# TD4Lite.net
KiCad netlist of a schematic drawn in EAGLE
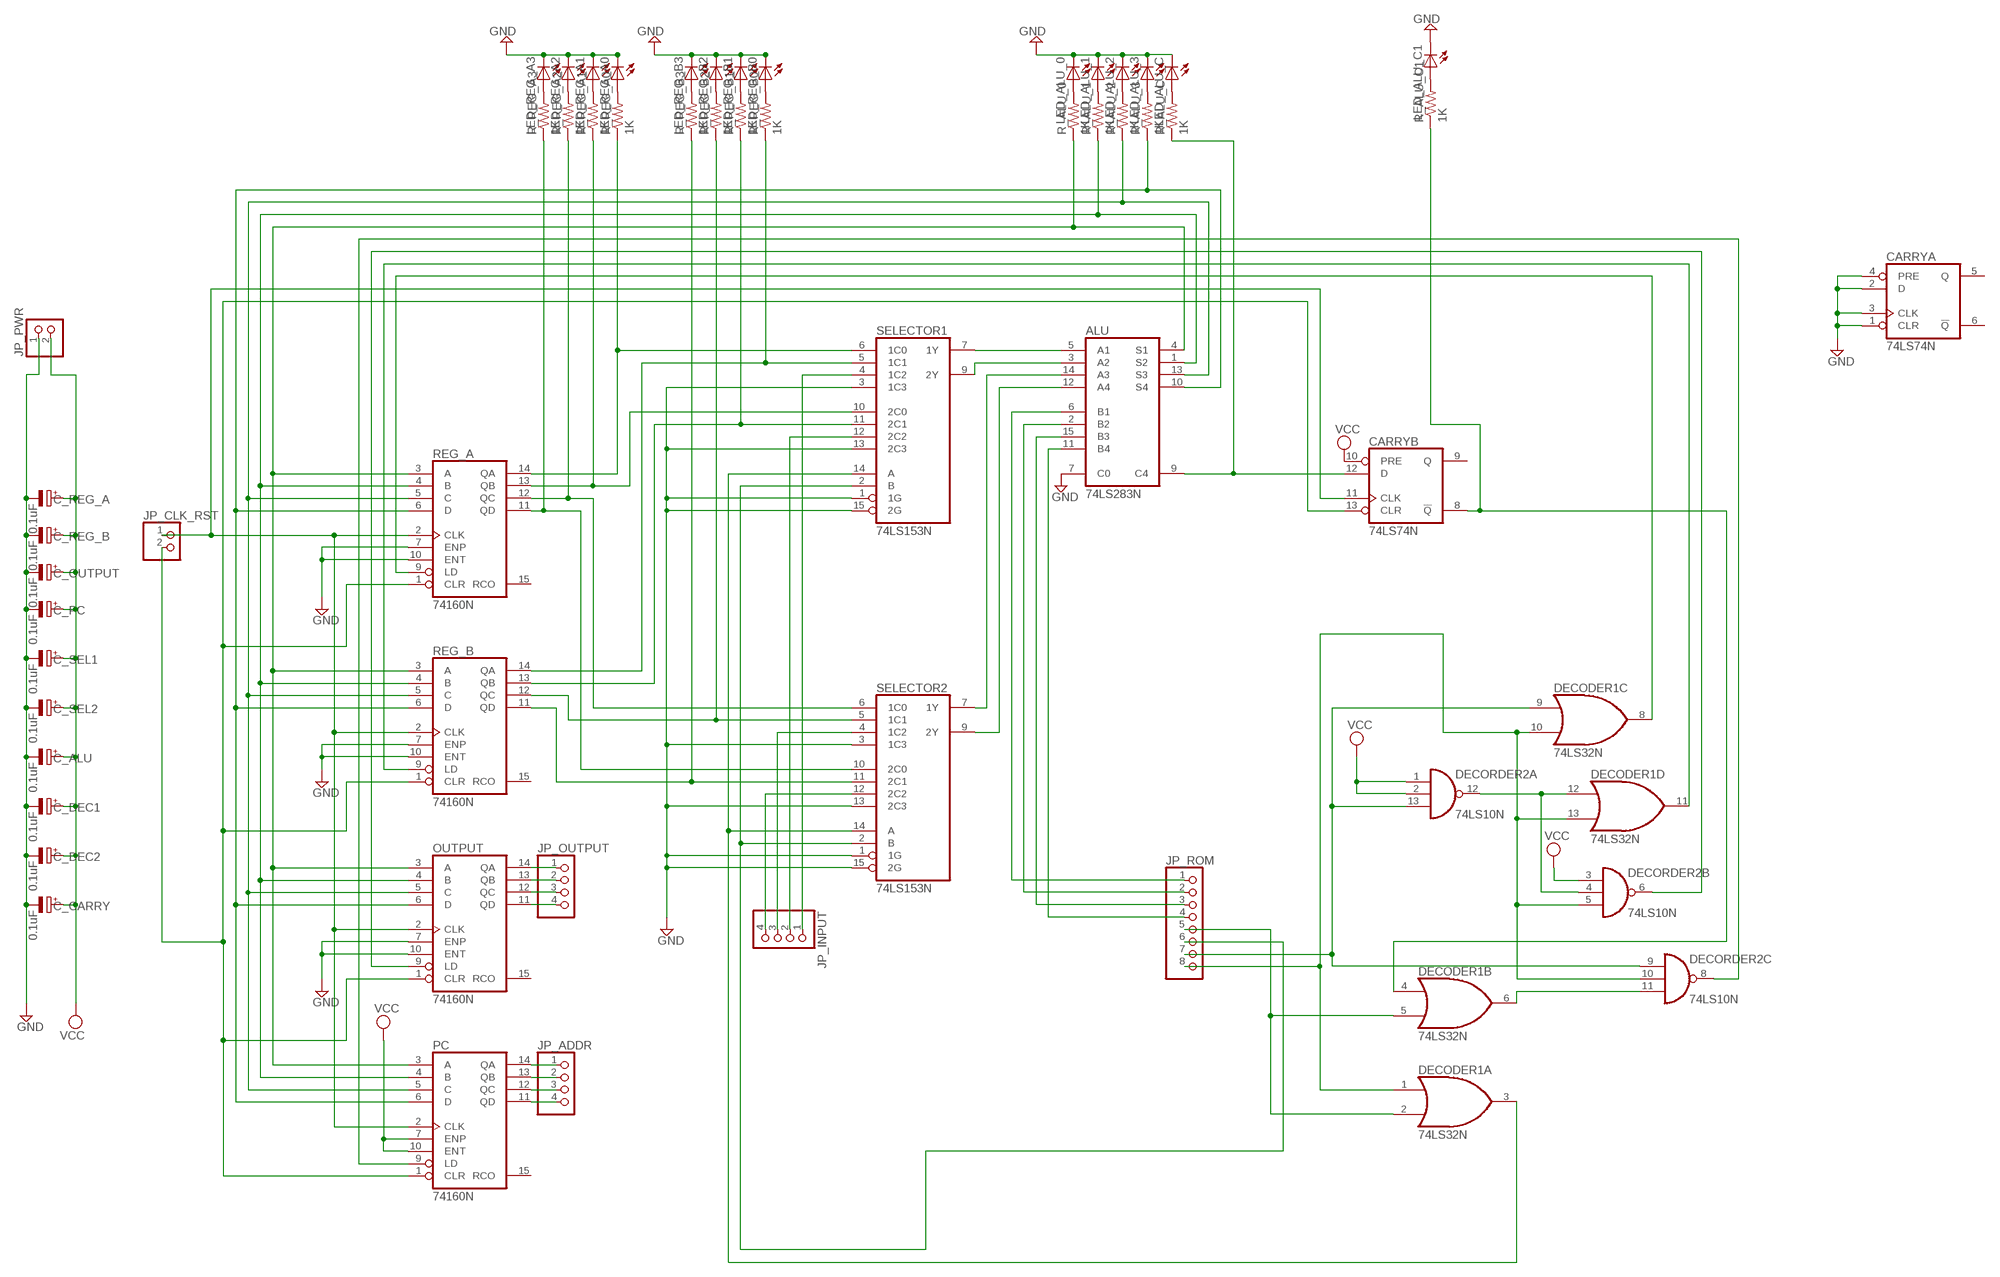
[diagram p0: schematic, sheet 1]

(export (version "E")
  (design (tool "Eeschema 10.0.6"))
  (components
    (comp (ref "ALU")
      (value "74LS283N")
      (footprint "eagle-import:DIL16")
      (libsource (lib "eagle-import") (part "74283NLS"))
    )
    (comp (ref "CARRY")
      (value "74LS74N")
      (footprint "eagle-import:DIL14")
      (libsource (lib "eagle-import") (part "7474NLS"))
    )
    (comp (ref "C_ALU")
      (value "0.1uF")
      (footprint "eagle-import:E2-5")
      (libsource (lib "eagle-import") (part "CPOL-EUE2-5"))
    )
    (comp (ref "C_CARRY")
      (value "0.1uF")
      (footprint "eagle-import:E2-5")
      (libsource (lib "eagle-import") (part "CPOL-EUE2-5"))
    )
    (comp (ref "C_DEC1")
      (value "0.1uF")
      (footprint "eagle-import:E2-5")
      (libsource (lib "eagle-import") (part "CPOL-EUE2-5"))
    )
    (comp (ref "C_DEC2")
      (value "0.1uF")
      (footprint "eagle-import:E2-5")
      (libsource (lib "eagle-import") (part "CPOL-EUE2-5"))
    )
    (comp (ref "C_OUTPUT")
      (value "0.1uF")
      (footprint "eagle-import:E2-5")
      (libsource (lib "eagle-import") (part "CPOL-EUE2-5"))
    )
    (comp (ref "C_PC")
      (value "0.1uF")
      (footprint "eagle-import:E2-5")
      (libsource (lib "eagle-import") (part "CPOL-EUE2-5"))
    )
    (comp (ref "C_REG_A")
      (value "0.1uF")
      (footprint "eagle-import:E2-5")
      (libsource (lib "eagle-import") (part "CPOL-EUE2-5"))
    )
    (comp (ref "C_REG_B")
      (value "0.1uF")
      (footprint "eagle-import:E2-5")
      (libsource (lib "eagle-import") (part "CPOL-EUE2-5"))
    )
    (comp (ref "C_SEL1")
      (value "0.1uF")
      (footprint "eagle-import:E2-5")
      (libsource (lib "eagle-import") (part "CPOL-EUE2-5"))
    )
    (comp (ref "C_SEL2")
      (value "0.1uF")
      (footprint "eagle-import:E2-5")
      (libsource (lib "eagle-import") (part "CPOL-EUE2-5"))
    )
    (comp (ref "DECODER1")
      (value "74LS32N")
      (footprint "eagle-import:DIL14")
      (libsource (lib "eagle-import") (part "7432NLS"))
    )
    (comp (ref "DECORDER2")
      (value "74LS10N")
      (footprint "eagle-import:DIL14")
      (libsource (lib "eagle-import") (part "7410NLS"))
    )
    (comp (ref "JP_ADDR")
      (value "PINHD-1X4")
      (footprint "eagle-import:1X04")
      (libsource (lib "eagle-import") (part "PINHD-1X4"))
    )
    (comp (ref "JP_CLK_RST")
      (value "PINHD-1X2")
      (footprint "eagle-import:1X02")
      (libsource (lib "eagle-import") (part "PINHD-1X2"))
    )
    (comp (ref "JP_INPUT")
      (value "PINHD-1X4")
      (footprint "eagle-import:1X04")
      (libsource (lib "eagle-import") (part "PINHD-1X4"))
    )
    (comp (ref "JP_OUTPUT")
      (value "PINHD-1X4")
      (footprint "eagle-import:1X04")
      (libsource (lib "eagle-import") (part "PINHD-1X4"))
    )
    (comp (ref "JP_PWR")
      (value "PINHD-1X2")
      (footprint "eagle-import:1X02")
      (libsource (lib "eagle-import") (part "PINHD-1X2"))
    )
    (comp (ref "JP_ROM")
      (value "PINHD-1X8")
      (footprint "eagle-import:1X08")
      (libsource (lib "eagle-import") (part "PINHD-1X8"))
    )
    (comp (ref "LED_ALU_0")
      (value "LED5MM")
      (footprint "eagle-import:LED5MM")
      (libsource (lib "eagle-import") (part "LED5MM"))
    )
    (comp (ref "LED_ALU_1")
      (value "LED5MM")
      (footprint "eagle-import:LED5MM")
      (libsource (lib "eagle-import") (part "LED5MM"))
    )
    (comp (ref "LED_ALU_2")
      (value "LED5MM")
      (footprint "eagle-import:LED5MM")
      (libsource (lib "eagle-import") (part "LED5MM"))
    )
    (comp (ref "LED_ALU_3")
      (value "LED5MM")
      (footprint "eagle-import:LED5MM")
      (libsource (lib "eagle-import") (part "LED5MM"))
    )
    (comp (ref "LED_ALU_C")
      (value "LED5MM")
      (footprint "eagle-import:LED5MM")
      (libsource (lib "eagle-import") (part "LED5MM"))
    )
    (comp (ref "LED_ALU_C1")
      (value "LED5MM")
      (footprint "eagle-import:LED5MM")
      (libsource (lib "eagle-import") (part "LED5MM"))
    )
    (comp (ref "LED_REG_A0")
      (value "LED5MM")
      (footprint "eagle-import:LED5MM")
      (libsource (lib "eagle-import") (part "LED5MM"))
    )
    (comp (ref "LED_REG_A1")
      (value "LED5MM")
      (footprint "eagle-import:LED5MM")
      (libsource (lib "eagle-import") (part "LED5MM"))
    )
    (comp (ref "LED_REG_A2")
      (value "LED5MM")
      (footprint "eagle-import:LED5MM")
      (libsource (lib "eagle-import") (part "LED5MM"))
    )
    (comp (ref "LED_REG_A3")
      (value "LED5MM")
      (footprint "eagle-import:LED5MM")
      (libsource (lib "eagle-import") (part "LED5MM"))
    )
    (comp (ref "LED_REG_B0")
      (value "LED5MM")
      (footprint "eagle-import:LED5MM")
      (libsource (lib "eagle-import") (part "LED5MM"))
    )
    (comp (ref "LED_REG_B1")
      (value "LED5MM")
      (footprint "eagle-import:LED5MM")
      (libsource (lib "eagle-import") (part "LED5MM"))
    )
    (comp (ref "LED_REG_B2")
      (value "LED5MM")
      (footprint "eagle-import:LED5MM")
      (libsource (lib "eagle-import") (part "LED5MM"))
    )
    (comp (ref "LED_REG_B3")
      (value "LED5MM")
      (footprint "eagle-import:LED5MM")
      (libsource (lib "eagle-import") (part "LED5MM"))
    )
    (comp (ref "OUTPUT")
      (value "74160N")
      (footprint "eagle-import:DIL16")
      (libsource (lib "eagle-import") (part "74160N"))
    )
    (comp (ref "PC")
      (value "74160N")
      (footprint "eagle-import:DIL16")
      (libsource (lib "eagle-import") (part "74160N"))
    )
    (comp (ref "REG_A")
      (value "74160N")
      (footprint "eagle-import:DIL16")
      (libsource (lib "eagle-import") (part "74160N"))
    )
    (comp (ref "REG_B")
      (value "74160N")
      (footprint "eagle-import:DIL16")
      (libsource (lib "eagle-import") (part "74160N"))
    )
    (comp (ref "R_ALU_0")
      (value "1K")
      (footprint "eagle-import:0204_7")
      (libsource (lib "eagle-import") (part "R-US_0204/7"))
    )
    (comp (ref "R_ALU_1")
      (value "1K")
      (footprint "eagle-import:0204_7")
      (libsource (lib "eagle-import") (part "R-US_0204/7"))
    )
    (comp (ref "R_ALU_2")
      (value "1K")
      (footprint "eagle-import:0204_7")
      (libsource (lib "eagle-import") (part "R-US_0204/7"))
    )
    (comp (ref "R_ALU_3")
      (value "1K")
      (footprint "eagle-import:0204_7")
      (libsource (lib "eagle-import") (part "R-US_0204/7"))
    )
    (comp (ref "R_ALU_C")
      (value "1K")
      (footprint "eagle-import:0204_7")
      (libsource (lib "eagle-import") (part "R-US_0204/7"))
    )
    (comp (ref "R_ALU_C1")
      (value "1K")
      (footprint "eagle-import:0204_7")
      (libsource (lib "eagle-import") (part "R-US_0204/7"))
    )
    (comp (ref "R_REG_A0")
      (value "1K")
      (footprint "eagle-import:0204_7")
      (libsource (lib "eagle-import") (part "R-US_0204/7"))
    )
    (comp (ref "R_REG_A1")
      (value "1K")
      (footprint "eagle-import:0204_7")
      (libsource (lib "eagle-import") (part "R-US_0204/7"))
    )
    (comp (ref "R_REG_A2")
      (value "1K")
      (footprint "eagle-import:0204_7")
      (libsource (lib "eagle-import") (part "R-US_0204/7"))
    )
    (comp (ref "R_REG_A3")
      (value "1K")
      (footprint "eagle-import:0204_7")
      (libsource (lib "eagle-import") (part "R-US_0204/7"))
    )
    (comp (ref "R_REG_B0")
      (value "1K")
      (footprint "eagle-import:0204_7")
      (libsource (lib "eagle-import") (part "R-US_0204/7"))
    )
    (comp (ref "R_REG_B1")
      (value "1K")
      (footprint "eagle-import:0204_7")
      (libsource (lib "eagle-import") (part "R-US_0204/7"))
    )
    (comp (ref "R_REG_B2")
      (value "1K")
      (footprint "eagle-import:0204_7")
      (libsource (lib "eagle-import") (part "R-US_0204/7"))
    )
    (comp (ref "R_REG_B3")
      (value "1K")
      (footprint "eagle-import:0204_7")
      (libsource (lib "eagle-import") (part "R-US_0204/7"))
    )
    (comp (ref "SELECTOR1")
      (value "74LS153N")
      (footprint "eagle-import:DIL16")
      (libsource (lib "eagle-import") (part "74153NLS"))
    )
    (comp (ref "SELECTOR2")
      (value "74LS153N")
      (footprint "eagle-import:DIL16")
      (libsource (lib "eagle-import") (part "74153NLS"))
    )
  )
  (nets
    (net (code "1") (name "GND") (class "Default")
      (node (ref "ALU") (pin "7") (pinfunction "C0_7") (pintype "input"))
      (node (ref "CARRY") (pin "1") (pinfunction "CLR_1") (pintype "input"))
      (node (ref "CARRY") (pin "2") (pinfunction "D_2") (pintype "input"))
      (node (ref "CARRY") (pin "3") (pinfunction "CLK_3") (pintype "input"))
      (node (ref "CARRY") (pin "4") (pinfunction "PRE_4") (pintype "input"))
      (node (ref "C_ALU") (pin "-") (pinfunction "-_-") (pintype "passive"))
      (node (ref "C_CARRY") (pin "-") (pinfunction "-_-") (pintype "passive"))
      (node (ref "C_DEC1") (pin "-") (pinfunction "-_-") (pintype "passive"))
      (node (ref "C_DEC2") (pin "-") (pinfunction "-_-") (pintype "passive"))
      (node (ref "C_OUTPUT") (pin "-") (pinfunction "-_-") (pintype "passive"))
      (node (ref "C_PC") (pin "-") (pinfunction "-_-") (pintype "passive"))
      (node (ref "C_REG_A") (pin "-") (pinfunction "-_-") (pintype "passive"))
      (node (ref "C_REG_B") (pin "-") (pinfunction "-_-") (pintype "passive"))
      (node (ref "C_SEL1") (pin "-") (pinfunction "-_-") (pintype "passive"))
      (node (ref "C_SEL2") (pin "-") (pinfunction "-_-") (pintype "passive"))
      (node (ref "JP_PWR") (pin "1") (pinfunction "1_1") (pintype "passive"))
      (node (ref "LED_ALU_0") (pin "K") (pinfunction "C_K") (pintype "passive"))
      (node (ref "LED_ALU_1") (pin "K") (pinfunction "C_K") (pintype "passive"))
      (node (ref "LED_ALU_2") (pin "K") (pinfunction "C_K") (pintype "passive"))
      (node (ref "LED_ALU_3") (pin "K") (pinfunction "C_K") (pintype "passive"))
      (node (ref "LED_ALU_C") (pin "K") (pinfunction "C_K") (pintype "passive"))
      (node (ref "LED_ALU_C1") (pin "K") (pinfunction "C_K") (pintype "passive"))
      (node (ref "LED_REG_A0") (pin "K") (pinfunction "C_K") (pintype "passive"))
      (node (ref "LED_REG_A1") (pin "K") (pinfunction "C_K") (pintype "passive"))
      (node (ref "LED_REG_A2") (pin "K") (pinfunction "C_K") (pintype "passive"))
      (node (ref "LED_REG_A3") (pin "K") (pinfunction "C_K") (pintype "passive"))
      (node (ref "LED_REG_B0") (pin "K") (pinfunction "C_K") (pintype "passive"))
      (node (ref "LED_REG_B1") (pin "K") (pinfunction "C_K") (pintype "passive"))
      (node (ref "LED_REG_B2") (pin "K") (pinfunction "C_K") (pintype "passive"))
      (node (ref "LED_REG_B3") (pin "K") (pinfunction "C_K") (pintype "passive"))
      (node (ref "OUTPUT") (pin "10") (pinfunction "ENT_10") (pintype "input"))
      (node (ref "OUTPUT") (pin "7") (pinfunction "ENP_7") (pintype "input"))
      (node (ref "REG_A") (pin "10") (pinfunction "ENT_10") (pintype "input"))
      (node (ref "REG_A") (pin "7") (pinfunction "ENP_7") (pintype "input"))
      (node (ref "REG_B") (pin "10") (pinfunction "ENT_10") (pintype "input"))
      (node (ref "REG_B") (pin "7") (pinfunction "ENP_7") (pintype "input"))
      (node (ref "SELECTOR1") (pin "1") (pinfunction "1G_1") (pintype "input"))
      (node (ref "SELECTOR1") (pin "13") (pinfunction "2C3_13") (pintype "input"))
      (node (ref "SELECTOR1") (pin "15") (pinfunction "2G_15") (pintype "input"))
      (node (ref "SELECTOR1") (pin "3") (pinfunction "1C3_3") (pintype "input"))
      (node (ref "SELECTOR2") (pin "1") (pinfunction "1G_1") (pintype "input"))
      (node (ref "SELECTOR2") (pin "13") (pinfunction "2C3_13") (pintype "input"))
      (node (ref "SELECTOR2") (pin "15") (pinfunction "2G_15") (pintype "input"))
      (node (ref "SELECTOR2") (pin "3") (pinfunction "1C3_3") (pintype "input"))
    )
    (net (code "2") (name "Net-(ALUA-A1)") (class "Default")
      (node (ref "ALU") (pin "5") (pinfunction "A1_5") (pintype "input"))
      (node (ref "SELECTOR1") (pin "7") (pinfunction "1Y_7") (pintype "output"))
    )
    (net (code "3") (name "Net-(ALUA-A2)") (class "Default")
      (node (ref "ALU") (pin "3") (pinfunction "A2_3") (pintype "input"))
      (node (ref "SELECTOR1") (pin "9") (pinfunction "2Y_9") (pintype "output"))
    )
    (net (code "4") (name "Net-(ALUA-A3)") (class "Default")
      (node (ref "ALU") (pin "14") (pinfunction "A3_14") (pintype "input"))
      (node (ref "SELECTOR2") (pin "7") (pinfunction "1Y_7") (pintype "output"))
    )
    (net (code "5") (name "Net-(ALUA-A4)") (class "Default")
      (node (ref "ALU") (pin "12") (pinfunction "A4_12") (pintype "input"))
      (node (ref "SELECTOR2") (pin "9") (pinfunction "2Y_9") (pintype "output"))
    )
    (net (code "6") (name "Net-(ALUA-B1)") (class "Default")
      (node (ref "ALU") (pin "6") (pinfunction "B1_6") (pintype "input"))
      (node (ref "JP_ROM") (pin "1") (pinfunction "1_1") (pintype "passive"))
    )
    (net (code "7") (name "Net-(ALUA-B2)") (class "Default")
      (node (ref "ALU") (pin "2") (pinfunction "B2_2") (pintype "input"))
      (node (ref "JP_ROM") (pin "2") (pinfunction "2_2") (pintype "passive"))
    )
    (net (code "8") (name "Net-(ALUA-B3)") (class "Default")
      (node (ref "ALU") (pin "15") (pinfunction "B3_15") (pintype "input"))
      (node (ref "JP_ROM") (pin "3") (pinfunction "3_3") (pintype "passive"))
    )
    (net (code "9") (name "Net-(ALUA-B4)") (class "Default")
      (node (ref "ALU") (pin "11") (pinfunction "B4_11") (pintype "input"))
      (node (ref "JP_ROM") (pin "4") (pinfunction "4_4") (pintype "passive"))
    )
    (net (code "10") (name "Net-(ALUA-C4)") (class "Default")
      (node (ref "ALU") (pin "9") (pinfunction "C4_9") (pintype "output"))
      (node (ref "CARRY") (pin "12") (pinfunction "D_12") (pintype "input"))
      (node (ref "R_ALU_C") (pin "1") (pinfunction "1_1") (pintype "passive"))
    )
    (net (code "11") (name "Net-(ALUA-S1)") (class "Default")
      (node (ref "ALU") (pin "4") (pinfunction "S1_4") (pintype "output"))
      (node (ref "OUTPUT") (pin "3") (pinfunction "A_3") (pintype "input"))
      (node (ref "PC") (pin "3") (pinfunction "A_3") (pintype "input"))
      (node (ref "REG_A") (pin "3") (pinfunction "A_3") (pintype "input"))
      (node (ref "REG_B") (pin "3") (pinfunction "A_3") (pintype "input"))
      (node (ref "R_ALU_0") (pin "1") (pinfunction "1_1") (pintype "passive"))
    )
    (net (code "12") (name "Net-(ALUA-S2)") (class "Default")
      (node (ref "ALU") (pin "1") (pinfunction "S2_1") (pintype "output"))
      (node (ref "OUTPUT") (pin "4") (pinfunction "B_4") (pintype "input"))
      (node (ref "PC") (pin "4") (pinfunction "B_4") (pintype "input"))
      (node (ref "REG_A") (pin "4") (pinfunction "B_4") (pintype "input"))
      (node (ref "REG_B") (pin "4") (pinfunction "B_4") (pintype "input"))
      (node (ref "R_ALU_1") (pin "1") (pinfunction "1_1") (pintype "passive"))
    )
    (net (code "13") (name "Net-(ALUA-S3)") (class "Default")
      (node (ref "ALU") (pin "13") (pinfunction "S3_13") (pintype "output"))
      (node (ref "OUTPUT") (pin "5") (pinfunction "C_5") (pintype "input"))
      (node (ref "PC") (pin "5") (pinfunction "C_5") (pintype "input"))
      (node (ref "REG_A") (pin "5") (pinfunction "C_5") (pintype "input"))
      (node (ref "REG_B") (pin "5") (pinfunction "C_5") (pintype "input"))
      (node (ref "R_ALU_2") (pin "1") (pinfunction "1_1") (pintype "passive"))
    )
    (net (code "14") (name "Net-(ALUA-S4)") (class "Default")
      (node (ref "ALU") (pin "10") (pinfunction "S4_10") (pintype "output"))
      (node (ref "OUTPUT") (pin "6") (pinfunction "D_6") (pintype "input"))
      (node (ref "PC") (pin "6") (pinfunction "D_6") (pintype "input"))
      (node (ref "REG_A") (pin "6") (pinfunction "D_6") (pintype "input"))
      (node (ref "REG_B") (pin "6") (pinfunction "D_6") (pintype "input"))
      (node (ref "R_ALU_3") (pin "1") (pinfunction "1_1") (pintype "passive"))
    )
    (net (code "15") (name "Net-(CARRYB-CLK)") (class "Default")
      (node (ref "CARRY") (pin "11") (pinfunction "CLK_11") (pintype "input"))
      (node (ref "JP_CLK_RST") (pin "1") (pinfunction "1_1") (pintype "passive"))
      (node (ref "OUTPUT") (pin "2") (pinfunction "CLK_2") (pintype "input"))
      (node (ref "PC") (pin "2") (pinfunction "CLK_2") (pintype "input"))
      (node (ref "REG_A") (pin "2") (pinfunction "CLK_2") (pintype "input"))
      (node (ref "REG_B") (pin "2") (pinfunction "CLK_2") (pintype "input"))
    )
    (net (code "16") (name "Net-(CARRYB-CLR)") (class "Default")
      (node (ref "CARRY") (pin "13") (pinfunction "CLR_13") (pintype "input"))
      (node (ref "JP_CLK_RST") (pin "2") (pinfunction "2_2") (pintype "passive"))
      (node (ref "OUTPUT") (pin "1") (pinfunction "CLR_1") (pintype "input"))
      (node (ref "PC") (pin "1") (pinfunction "CLR_1") (pintype "input"))
      (node (ref "REG_A") (pin "1") (pinfunction "CLR_1") (pintype "input"))
      (node (ref "REG_B") (pin "1") (pinfunction "CLR_1") (pintype "input"))
    )
    (net (code "17") (name "Net-(CARRYB-~{Q})") (class "Default")
      (node (ref "CARRY") (pin "8") (pinfunction "~{Q}_8") (pintype "output"))
      (node (ref "DECODER1") (pin "4") (pinfunction "I0_4") (pintype "input"))
      (node (ref "R_ALU_C1") (pin "1") (pinfunction "1_1") (pintype "passive"))
    )
    (net (code "18") (name "Net-(DECODER1A-I0)") (class "Default")
      (node (ref "DECODER1") (pin "1") (pinfunction "I0_1") (pintype "input"))
      (node (ref "DECODER1") (pin "10") (pinfunction "I1_10") (pintype "input"))
      (node (ref "DECODER1") (pin "13") (pinfunction "I1_13") (pintype "input"))
      (node (ref "DECORDER2") (pin "10") (pinfunction "I1_10") (pintype "input"))
      (node (ref "DECORDER2") (pin "5") (pinfunction "I2_5") (pintype "input"))
      (node (ref "JP_ROM") (pin "8") (pinfunction "8_8") (pintype "passive"))
    )
    (net (code "19") (name "Net-(DECODER1A-I1)") (class "Default")
      (node (ref "DECODER1") (pin "2") (pinfunction "I1_2") (pintype "input"))
      (node (ref "DECODER1") (pin "5") (pinfunction "I1_5") (pintype "input"))
      (node (ref "JP_ROM") (pin "5") (pinfunction "5_5") (pintype "passive"))
    )
    (net (code "20") (name "Net-(DECODER1A-O)") (class "Default")
      (node (ref "DECODER1") (pin "3") (pinfunction "O_3") (pintype "output"))
      (node (ref "SELECTOR1") (pin "14") (pinfunction "A_14") (pintype "input"))
      (node (ref "SELECTOR2") (pin "14") (pinfunction "A_14") (pintype "input"))
    )
    (net (code "21") (name "Net-(DECODER1B-O)") (class "Default")
      (node (ref "DECODER1") (pin "6") (pinfunction "O_6") (pintype "output"))
      (node (ref "DECORDER2") (pin "11") (pinfunction "I2_11") (pintype "input"))
    )
    (net (code "22") (name "Net-(DECODER1C-I0)") (class "Default")
      (node (ref "DECODER1") (pin "9") (pinfunction "I0_9") (pintype "input"))
      (node (ref "DECORDER2") (pin "13") (pinfunction "I2_13") (pintype "input"))
      (node (ref "DECORDER2") (pin "9") (pinfunction "I0_9") (pintype "input"))
      (node (ref "JP_ROM") (pin "7") (pinfunction "7_7") (pintype "passive"))
    )
    (net (code "23") (name "Net-(DECODER1C-O)") (class "Default")
      (node (ref "DECODER1") (pin "8") (pinfunction "O_8") (pintype "output"))
      (node (ref "REG_A") (pin "9") (pinfunction "LD_9") (pintype "input"))
    )
    (net (code "24") (name "Net-(DECODER1D-I0)") (class "Default")
      (node (ref "DECODER1") (pin "12") (pinfunction "I0_12") (pintype "input"))
      (node (ref "DECORDER2") (pin "12") (pinfunction "O_12") (pintype "output"))
      (node (ref "DECORDER2") (pin "4") (pinfunction "I1_4") (pintype "input"))
    )
    (net (code "25") (name "Net-(DECODER1D-O)") (class "Default")
      (node (ref "DECODER1") (pin "11") (pinfunction "O_11") (pintype "output"))
      (node (ref "REG_B") (pin "9") (pinfunction "LD_9") (pintype "input"))
    )
    (net (code "26") (name "Net-(DECORDER2B-O)") (class "Default")
      (node (ref "DECORDER2") (pin "6") (pinfunction "O_6") (pintype "output"))
      (node (ref "OUTPUT") (pin "9") (pinfunction "LD_9") (pintype "input"))
    )
    (net (code "27") (name "Net-(DECORDER2C-O)") (class "Default")
      (node (ref "DECORDER2") (pin "8") (pinfunction "O_8") (pintype "output"))
      (node (ref "PC") (pin "9") (pinfunction "LD_9") (pintype "input"))
    )
    (net (code "28") (name "Net-(LED_ALU_0-PadA)") (class "Default")
      (node (ref "LED_ALU_0") (pin "A") (pinfunction "A_A") (pintype "passive"))
      (node (ref "R_ALU_0") (pin "2") (pinfunction "2_2") (pintype "passive"))
    )
    (net (code "29") (name "Net-(LED_ALU_1-PadA)") (class "Default")
      (node (ref "LED_ALU_1") (pin "A") (pinfunction "A_A") (pintype "passive"))
      (node (ref "R_ALU_1") (pin "2") (pinfunction "2_2") (pintype "passive"))
    )
    (net (code "30") (name "Net-(LED_ALU_2-PadA)") (class "Default")
      (node (ref "LED_ALU_2") (pin "A") (pinfunction "A_A") (pintype "passive"))
      (node (ref "R_ALU_2") (pin "2") (pinfunction "2_2") (pintype "passive"))
    )
    (net (code "31") (name "Net-(LED_ALU_3-PadA)") (class "Default")
      (node (ref "LED_ALU_3") (pin "A") (pinfunction "A_A") (pintype "passive"))
      (node (ref "R_ALU_3") (pin "2") (pinfunction "2_2") (pintype "passive"))
    )
    (net (code "32") (name "Net-(LED_ALU_C-PadA)") (class "Default")
      (node (ref "LED_ALU_C") (pin "A") (pinfunction "A_A") (pintype "passive"))
      (node (ref "R_ALU_C") (pin "2") (pinfunction "2_2") (pintype "passive"))
    )
    (net (code "33") (name "Net-(LED_ALU_C1-PadA)") (class "Default")
      (node (ref "LED_ALU_C1") (pin "A") (pinfunction "A_A") (pintype "passive"))
      (node (ref "R_ALU_C1") (pin "2") (pinfunction "2_2") (pintype "passive"))
    )
    (net (code "34") (name "Net-(LED_REG_A0-PadA)") (class "Default")
      (node (ref "LED_REG_A0") (pin "A") (pinfunction "A_A") (pintype "passive"))
      (node (ref "R_REG_A0") (pin "2") (pinfunction "2_2") (pintype "passive"))
    )
    (net (code "35") (name "Net-(LED_REG_A1-PadA)") (class "Default")
      (node (ref "LED_REG_A1") (pin "A") (pinfunction "A_A") (pintype "passive"))
      (node (ref "R_REG_A1") (pin "2") (pinfunction "2_2") (pintype "passive"))
    )
    (net (code "36") (name "Net-(LED_REG_A2-PadA)") (class "Default")
      (node (ref "LED_REG_A2") (pin "A") (pinfunction "A_A") (pintype "passive"))
      (node (ref "R_REG_A2") (pin "2") (pinfunction "2_2") (pintype "passive"))
    )
    (net (code "37") (name "Net-(LED_REG_A3-PadA)") (class "Default")
      (node (ref "LED_REG_A3") (pin "A") (pinfunction "A_A") (pintype "passive"))
      (node (ref "R_REG_A3") (pin "2") (pinfunction "2_2") (pintype "passive"))
    )
    (net (code "38") (name "Net-(LED_REG_B0-PadA)") (class "Default")
      (node (ref "LED_REG_B0") (pin "A") (pinfunction "A_A") (pintype "passive"))
      (node (ref "R_REG_B0") (pin "2") (pinfunction "2_2") (pintype "passive"))
    )
    (net (code "39") (name "Net-(LED_REG_B1-PadA)") (class "Default")
      (node (ref "LED_REG_B1") (pin "A") (pinfunction "A_A") (pintype "passive"))
      (node (ref "R_REG_B1") (pin "2") (pinfunction "2_2") (pintype "passive"))
    )
    (net (code "40") (name "Net-(LED_REG_B2-PadA)") (class "Default")
      (node (ref "LED_REG_B2") (pin "A") (pinfunction "A_A") (pintype "passive"))
      (node (ref "R_REG_B2") (pin "2") (pinfunction "2_2") (pintype "passive"))
    )
    (net (code "41") (name "Net-(LED_REG_B3-PadA)") (class "Default")
      (node (ref "LED_REG_B3") (pin "A") (pinfunction "A_A") (pintype "passive"))
      (node (ref "R_REG_B3") (pin "2") (pinfunction "2_2") (pintype "passive"))
    )
    (net (code "42") (name "Net-(OUTPUTA-QA)") (class "Default")
      (node (ref "JP_OUTPUT") (pin "1") (pinfunction "1_1") (pintype "passive"))
      (node (ref "OUTPUT") (pin "14") (pinfunction "QA_14") (pintype "output"))
    )
    (net (code "43") (name "Net-(OUTPUTA-QB)") (class "Default")
      (node (ref "JP_OUTPUT") (pin "2") (pinfunction "2_2") (pintype "passive"))
      (node (ref "OUTPUT") (pin "13") (pinfunction "QB_13") (pintype "output"))
    )
    (net (code "44") (name "Net-(OUTPUTA-QC)") (class "Default")
      (node (ref "JP_OUTPUT") (pin "3") (pinfunction "3_3") (pintype "passive"))
      (node (ref "OUTPUT") (pin "12") (pinfunction "QC_12") (pintype "output"))
    )
    (net (code "45") (name "Net-(OUTPUTA-QD)") (class "Default")
      (node (ref "JP_OUTPUT") (pin "4") (pinfunction "4_4") (pintype "passive"))
      (node (ref "OUTPUT") (pin "11") (pinfunction "QD_11") (pintype "output"))
    )
    (net (code "46") (name "Net-(PCA-QA)") (class "Default")
      (node (ref "JP_ADDR") (pin "1") (pinfunction "1_1") (pintype "passive"))
      (node (ref "PC") (pin "14") (pinfunction "QA_14") (pintype "output"))
    )
    (net (code "47") (name "Net-(PCA-QB)") (class "Default")
      (node (ref "JP_ADDR") (pin "2") (pinfunction "2_2") (pintype "passive"))
      (node (ref "PC") (pin "13") (pinfunction "QB_13") (pintype "output"))
    )
    (net (code "48") (name "Net-(PCA-QC)") (class "Default")
      (node (ref "JP_ADDR") (pin "3") (pinfunction "3_3") (pintype "passive"))
      (node (ref "PC") (pin "12") (pinfunction "QC_12") (pintype "output"))
    )
    (net (code "49") (name "Net-(PCA-QD)") (class "Default")
      (node (ref "JP_ADDR") (pin "4") (pinfunction "4_4") (pintype "passive"))
      (node (ref "PC") (pin "11") (pinfunction "QD_11") (pintype "output"))
    )
    (net (code "50") (name "Net-(REG_AA-QA)") (class "Default")
      (node (ref "REG_A") (pin "14") (pinfunction "QA_14") (pintype "output"))
      (node (ref "R_REG_A0") (pin "1") (pinfunction "1_1") (pintype "passive"))
      (node (ref "SELECTOR1") (pin "6") (pinfunction "1C0_6") (pintype "input"))
    )
    (net (code "51") (name "Net-(REG_AA-QB)") (class "Default")
      (node (ref "REG_A") (pin "13") (pinfunction "QB_13") (pintype "output"))
      (node (ref "R_REG_A1") (pin "1") (pinfunction "1_1") (pintype "passive"))
      (node (ref "SELECTOR1") (pin "10") (pinfunction "2C0_10") (pintype "input"))
    )
    (net (code "52") (name "Net-(REG_AA-QC)") (class "Default")
      (node (ref "REG_A") (pin "12") (pinfunction "QC_12") (pintype "output"))
      (node (ref "R_REG_A2") (pin "1") (pinfunction "1_1") (pintype "passive"))
      (node (ref "SELECTOR2") (pin "6") (pinfunction "1C0_6") (pintype "input"))
    )
    (net (code "53") (name "Net-(REG_AA-QD)") (class "Default")
      (node (ref "REG_A") (pin "11") (pinfunction "QD_11") (pintype "output"))
      (node (ref "R_REG_A3") (pin "1") (pinfunction "1_1") (pintype "passive"))
      (node (ref "SELECTOR2") (pin "10") (pinfunction "2C0_10") (pintype "input"))
    )
    (net (code "54") (name "Net-(REG_BA-QA)") (class "Default")
      (node (ref "REG_B") (pin "14") (pinfunction "QA_14") (pintype "output"))
      (node (ref "R_REG_B0") (pin "1") (pinfunction "1_1") (pintype "passive"))
      (node (ref "SELECTOR1") (pin "5") (pinfunction "1C1_5") (pintype "input"))
    )
    (net (code "55") (name "Net-(REG_BA-QB)") (class "Default")
      (node (ref "REG_B") (pin "13") (pinfunction "QB_13") (pintype "output"))
      (node (ref "R_REG_B1") (pin "1") (pinfunction "1_1") (pintype "passive"))
      (node (ref "SELECTOR1") (pin "11") (pinfunction "2C1_11") (pintype "input"))
    )
    (net (code "56") (name "Net-(REG_BA-QC)") (class "Default")
      (node (ref "REG_B") (pin "12") (pinfunction "QC_12") (pintype "output"))
      (node (ref "R_REG_B2") (pin "1") (pinfunction "1_1") (pintype "passive"))
      (node (ref "SELECTOR2") (pin "5") (pinfunction "1C1_5") (pintype "input"))
    )
    (net (code "57") (name "Net-(REG_BA-QD)") (class "Default")
      (node (ref "REG_B") (pin "11") (pinfunction "QD_11") (pintype "output"))
      (node (ref "R_REG_B3") (pin "1") (pinfunction "1_1") (pintype "passive"))
      (node (ref "SELECTOR2") (pin "11") (pinfunction "2C1_11") (pintype "input"))
    )
    (net (code "58") (name "Net-(SELECTOR1A-1C2)") (class "Default")
      (node (ref "JP_INPUT") (pin "1") (pinfunction "1_1") (pintype "passive"))
      (node (ref "SELECTOR1") (pin "4") (pinfunction "1C2_4") (pintype "input"))
    )
    (net (code "59") (name "Net-(SELECTOR1A-2C2)") (class "Default")
      (node (ref "JP_INPUT") (pin "2") (pinfunction "2_2") (pintype "passive"))
      (node (ref "SELECTOR1") (pin "12") (pinfunction "2C2_12") (pintype "input"))
    )
    (net (code "60") (name "Net-(SELECTOR1A-B)") (class "Default")
      (node (ref "JP_ROM") (pin "6") (pinfunction "6_6") (pintype "passive"))
      (node (ref "SELECTOR1") (pin "2") (pinfunction "B_2") (pintype "input"))
      (node (ref "SELECTOR2") (pin "2") (pinfunction "B_2") (pintype "input"))
    )
    (net (code "61") (name "Net-(SELECTOR2A-1C2)") (class "Default")
      (node (ref "JP_INPUT") (pin "3") (pinfunction "3_3") (pintype "passive"))
      (node (ref "SELECTOR2") (pin "4") (pinfunction "1C2_4") (pintype "input"))
    )
    (net (code "62") (name "Net-(SELECTOR2A-2C2)") (class "Default")
      (node (ref "JP_INPUT") (pin "4") (pinfunction "4_4") (pintype "passive"))
      (node (ref "SELECTOR2") (pin "12") (pinfunction "2C2_12") (pintype "input"))
    )
    (net (code "63") (name "VCC") (class "Default")
      (node (ref "CARRY") (pin "10") (pinfunction "PRE_10") (pintype "input"))
      (node (ref "C_ALU") (pin "+") (pinfunction "+_+") (pintype "passive"))
      (node (ref "C_CARRY") (pin "+") (pinfunction "+_+") (pintype "passive"))
      (node (ref "C_DEC1") (pin "+") (pinfunction "+_+") (pintype "passive"))
      (node (ref "C_DEC2") (pin "+") (pinfunction "+_+") (pintype "passive"))
      (node (ref "C_OUTPUT") (pin "+") (pinfunction "+_+") (pintype "passive"))
      (node (ref "C_PC") (pin "+") (pinfunction "+_+") (pintype "passive"))
      (node (ref "C_REG_A") (pin "+") (pinfunction "+_+") (pintype "passive"))
      (node (ref "C_REG_B") (pin "+") (pinfunction "+_+") (pintype "passive"))
      (node (ref "C_SEL1") (pin "+") (pinfunction "+_+") (pintype "passive"))
      (node (ref "C_SEL2") (pin "+") (pinfunction "+_+") (pintype "passive"))
      (node (ref "DECORDER2") (pin "1") (pinfunction "I0_1") (pintype "input"))
      (node (ref "DECORDER2") (pin "2") (pinfunction "I1_2") (pintype "input"))
      (node (ref "DECORDER2") (pin "3") (pinfunction "I0_3") (pintype "input"))
      (node (ref "JP_PWR") (pin "2") (pinfunction "2_2") (pintype "passive"))
      (node (ref "PC") (pin "10") (pinfunction "ENT_10") (pintype "input"))
      (node (ref "PC") (pin "7") (pinfunction "ENP_7") (pintype "input"))
    )
    (net (code "64") (name "unconnected-(CARRYA-Q-Pad5)") (class "Default")
      (node (ref "CARRY") (pin "5") (pinfunction "Q_5") (pintype "output"))
    )
    (net (code "65") (name "unconnected-(CARRYA-~{Q}-Pad6)") (class "Default")
      (node (ref "CARRY") (pin "6") (pinfunction "~{Q}_6") (pintype "output"))
    )
    (net (code "66") (name "unconnected-(CARRYB-Q-Pad9)") (class "Default")
      (node (ref "CARRY") (pin "9") (pinfunction "Q_9") (pintype "output"))
    )
    (net (code "67") (name "unconnected-(OUTPUTA-RCO-Pad15)") (class "Default")
      (node (ref "OUTPUT") (pin "15") (pinfunction "RCO_15") (pintype "output"))
    )
    (net (code "68") (name "unconnected-(PCA-RCO-Pad15)") (class "Default")
      (node (ref "PC") (pin "15") (pinfunction "RCO_15") (pintype "output"))
    )
    (net (code "69") (name "unconnected-(REG_AA-RCO-Pad15)") (class "Default")
      (node (ref "REG_A") (pin "15") (pinfunction "RCO_15") (pintype "output"))
    )
    (net (code "70") (name "unconnected-(REG_BA-RCO-Pad15)") (class "Default")
      (node (ref "REG_B") (pin "15") (pinfunction "RCO_15") (pintype "output"))
    )
  )
)
